# T09_LockBox_ver6.net
KiCad netlist of a schematic drawn in EAGLE
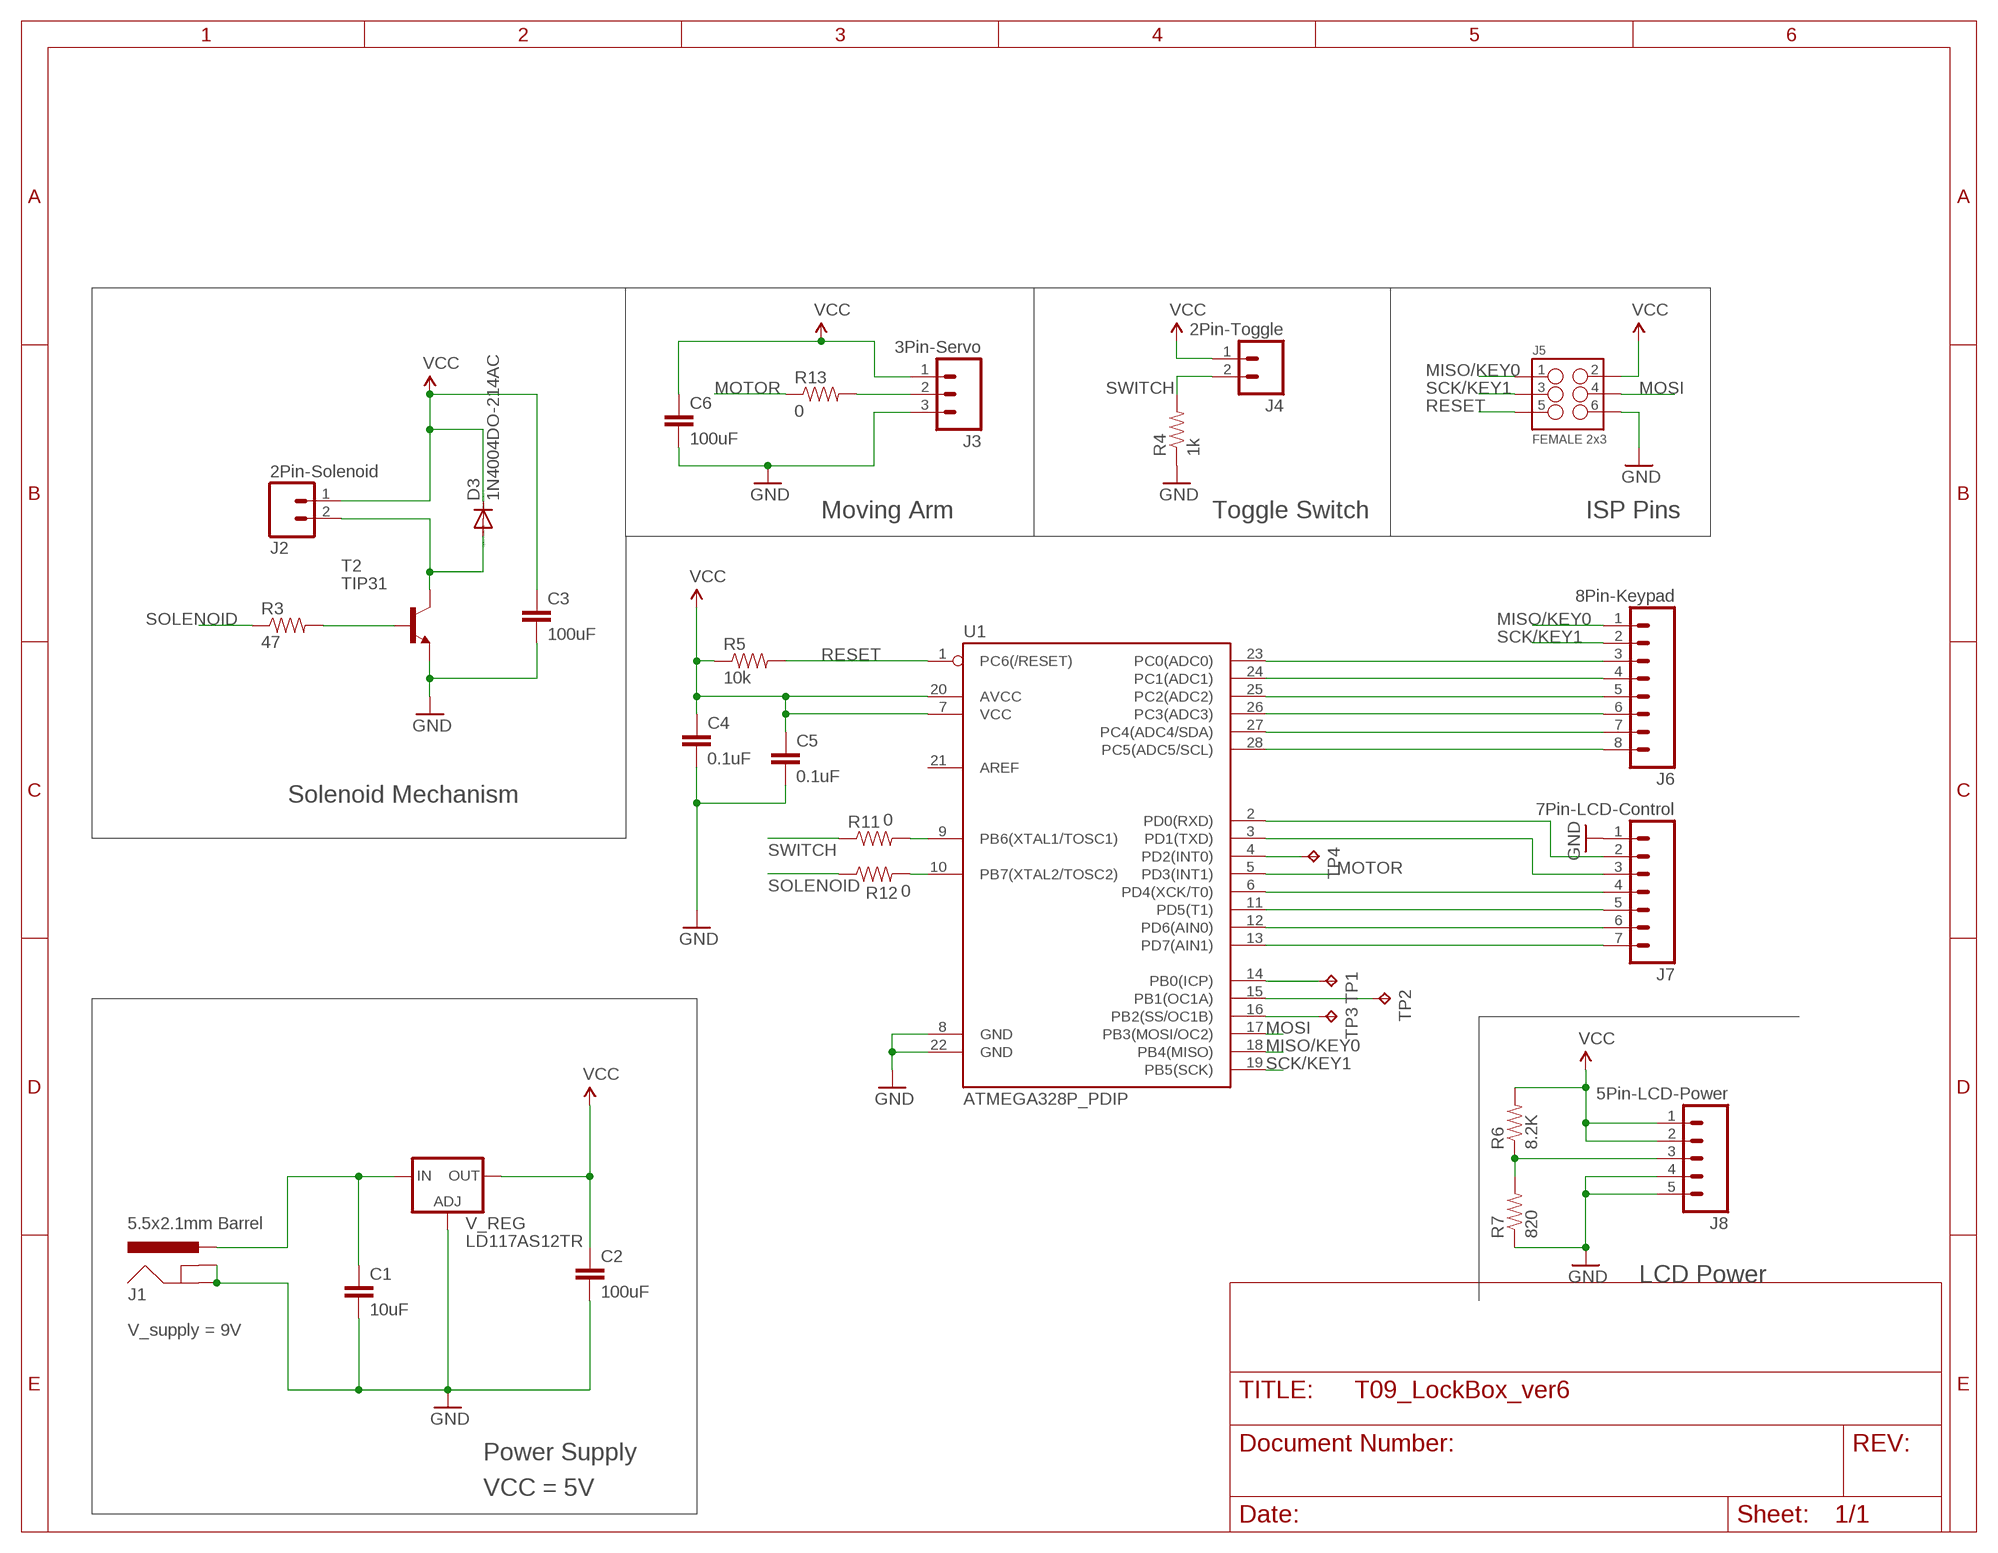
[diagram p0: schematic, sheet 1]

(export (version "E")
  (design (tool "Eeschema 10.0.6"))
  (components
    (comp (ref "C1")
      (value "10uF")
      (footprint "eagle-import:0603-CAP")
      (libsource (lib "eagle-import") (part "CAP0603-CAP"))
    )
    (comp (ref "C2")
      (value "100uF")
      (footprint "eagle-import:0603-CAP")
      (libsource (lib "eagle-import") (part "CAP0603-CAP"))
    )
    (comp (ref "C3")
      (value "100uF")
      (footprint "eagle-import:0603-CAP")
      (libsource (lib "eagle-import") (part "CAP0603-CAP"))
    )
    (comp (ref "C4")
      (value "0.1uF")
      (footprint "eagle-import:0603-CAP")
      (libsource (lib "eagle-import") (part "CAP0603-CAP"))
    )
    (comp (ref "C5")
      (value "0.1uF")
      (footprint "eagle-import:0603-CAP")
      (libsource (lib "eagle-import") (part "CAP0603-CAP"))
    )
    (comp (ref "C6")
      (value "100uF")
      (footprint "eagle-import:0603-CAP")
      (libsource (lib "eagle-import") (part "CAP0603-CAP"))
    )
    (comp (ref "D3")
      (value "1N4004DO-214AC")
      (footprint "eagle-import:DO-214AC")
      (libsource (lib "eagle-import") (part "1N4004DO-214AC"))
    )
    (comp (ref "J1")
      (value "5.5x2.1mm Barrel")
      (footprint "eagle-import:POWER_JACK_SMD")
      (libsource (lib "eagle-import") (part "POWER_JACKSMD"))
    )
    (comp (ref "J2")
      (value "2Pin-Solenoid")
      (footprint "eagle-import:1X02")
      (libsource (lib "eagle-import") (part "M02PTH"))
    )
    (comp (ref "J3")
      (value "3Pin-Servo")
      (footprint "eagle-import:1X03")
      (libsource (lib "eagle-import") (part "M03PTH"))
    )
    (comp (ref "J4")
      (value "2Pin-Toggle")
      (footprint "eagle-import:1X02")
      (libsource (lib "eagle-import") (part "M02PTH"))
    )
    (comp (ref "J5")
      (value "FEMALE 2x3")
      (footprint "eagle-import:2X3")
      (libsource (lib "eagle-import") (part "M03X2FEMALE"))
    )
    (comp (ref "J6")
      (value "8Pin-Keypad")
      (footprint "eagle-import:1X08_ROUND")
      (libsource (lib "eagle-import") (part "M08"))
    )
    (comp (ref "J7")
      (value "7Pin-LCD-Control")
      (footprint "eagle-import:1X07")
      (libsource (lib "eagle-import") (part "M07"))
    )
    (comp (ref "J8")
      (value "5Pin-LCD-Power")
      (footprint "eagle-import:1X05")
      (libsource (lib "eagle-import") (part "M05PTH"))
    )
    (comp (ref "R3")
      (value "47")
      (footprint "eagle-import:0805")
      (libsource (lib "eagle-import") (part "RESISTOR0805-RES"))
    )
    (comp (ref "R4")
      (value "1k")
      (footprint "eagle-import:0603-RES")
      (libsource (lib "eagle-import") (part "RESISTOR0603"))
    )
    (comp (ref "R5")
      (value "10k")
      (footprint "eagle-import:0603-RES")
      (libsource (lib "eagle-import") (part "RESISTOR0603"))
    )
    (comp (ref "R6")
      (value "8.2K")
      (footprint "eagle-import:0603-RES")
      (libsource (lib "eagle-import") (part "RESISTOR0603"))
    )
    (comp (ref "R7")
      (value "820")
      (footprint "eagle-import:0603-RES")
      (libsource (lib "eagle-import") (part "RESISTOR0603"))
    )
    (comp (ref "R11")
      (value "0")
      (footprint "eagle-import:0603-RES")
      (libsource (lib "eagle-import") (part "RESISTOR0603"))
    )
    (comp (ref "R12")
      (value "0")
      (footprint "eagle-import:0603-RES")
      (libsource (lib "eagle-import") (part "RESISTOR0603"))
    )
    (comp (ref "R13")
      (value "0")
      (footprint "eagle-import:0603-RES")
      (libsource (lib "eagle-import") (part "RESISTOR0603"))
    )
    (comp (ref "T2")
      (value "TIP31")
      (footprint "eagle-import:TO220")
      (libsource (lib "eagle-import") (part "TIP31"))
    )
    (comp (ref "TP1")
      (value "TPPAD1-13")
      (footprint "eagle-import:P1-13")
      (libsource (lib "eagle-import") (part "TPPAD1-13"))
    )
    (comp (ref "TP2")
      (value "TPPAD1-13")
      (footprint "eagle-import:P1-13")
      (libsource (lib "eagle-import") (part "TPPAD1-13"))
    )
    (comp (ref "TP3")
      (value "TPPAD1-13")
      (footprint "eagle-import:P1-13")
      (libsource (lib "eagle-import") (part "TPPAD1-13"))
    )
    (comp (ref "TP4")
      (value "TPPAD1-13")
      (footprint "eagle-import:P1-13")
      (libsource (lib "eagle-import") (part "TPPAD1-13"))
    )
    (comp (ref "U1")
      (value "ATMEGA328P_PDIP")
      (footprint "eagle-import:DIL28-3")
      (libsource (lib "eagle-import") (part "ATMEGA328P_PDIP"))
    )
    (comp (ref "V_REG")
      (value "LD117AS12TR")
      (footprint "eagle-import:SOT223")
      (libsource (lib "eagle-import") (part "LD117A?S12TR"))
    )
  )
  (nets
    (net (code "1") (name "/MISO{slash}KEY0") (class "Default")
      (node (ref "J5") (pin "1") (pinfunction "1_1") (pintype "bidirectional"))
      (node (ref "J6") (pin "1") (pinfunction "1_1") (pintype "passive"))
      (node (ref "U1") (pin "18") (pinfunction "PB4(MISO)_18") (pintype "bidirectional"))
    )
    (net (code "2") (name "/MOSI") (class "Default")
      (node (ref "J5") (pin "4") (pinfunction "4_4") (pintype "bidirectional"))
      (node (ref "U1") (pin "17") (pinfunction "PB3(MOSI/OC2)_17") (pintype "bidirectional"))
    )
    (net (code "3") (name "/MOTOR") (class "Default")
      (node (ref "R13") (pin "1") (pinfunction "1_1") (pintype "passive"))
      (node (ref "U1") (pin "5") (pinfunction "PD3(INT1)_5") (pintype "bidirectional"))
    )
    (net (code "4") (name "/RESET") (class "Default")
      (node (ref "J5") (pin "5") (pinfunction "5_5") (pintype "bidirectional"))
      (node (ref "R5") (pin "2") (pinfunction "2_2") (pintype "passive"))
      (node (ref "U1") (pin "1") (pinfunction "PC6(/RESET)_1") (pintype "bidirectional"))
    )
    (net (code "5") (name "/SCK{slash}KEY1") (class "Default")
      (node (ref "J5") (pin "3") (pinfunction "3_3") (pintype "bidirectional"))
      (node (ref "J6") (pin "2") (pinfunction "2_2") (pintype "passive"))
      (node (ref "U1") (pin "19") (pinfunction "PB5(SCK)_19") (pintype "bidirectional"))
    )
    (net (code "6") (name "/SOLENOID") (class "Default")
      (node (ref "R12") (pin "1") (pinfunction "1_1") (pintype "passive"))
      (node (ref "R3") (pin "1") (pinfunction "1_1") (pintype "passive"))
    )
    (net (code "7") (name "/SWITCH") (class "Default")
      (node (ref "J4") (pin "2") (pinfunction "2_2") (pintype "passive"))
      (node (ref "R11") (pin "1") (pinfunction "1_1") (pintype "passive"))
      (node (ref "R4") (pin "2") (pinfunction "2_2") (pintype "passive"))
    )
    (net (code "8") (name "GND") (class "Default")
      (node (ref "C1") (pin "2") (pinfunction "2_2") (pintype "passive"))
      (node (ref "C2") (pin "2") (pinfunction "2_2") (pintype "passive"))
      (node (ref "C3") (pin "2") (pinfunction "2_2") (pintype "passive"))
      (node (ref "C4") (pin "2") (pinfunction "2_2") (pintype "passive"))
      (node (ref "C5") (pin "2") (pinfunction "2_2") (pintype "passive"))
      (node (ref "C6") (pin "2") (pinfunction "2_2") (pintype "passive"))
      (node (ref "J1") (pin "GND") (pinfunction "GNDBREAK_GND") (pintype "bidirectional"))
      (node (ref "J1") (pin "P$4") (pinfunction "GND_P$4") (pintype "bidirectional"))
      (node (ref "J3") (pin "3") (pinfunction "3_3") (pintype "passive"))
      (node (ref "J5") (pin "6") (pinfunction "6_6") (pintype "bidirectional"))
      (node (ref "J7") (pin "1") (pinfunction "1_1") (pintype "passive"))
      (node (ref "J8") (pin "4") (pinfunction "4_4") (pintype "passive"))
      (node (ref "J8") (pin "5") (pinfunction "5_5") (pintype "passive"))
      (node (ref "R4") (pin "1") (pinfunction "1_1") (pintype "passive"))
      (node (ref "R7") (pin "1") (pinfunction "1_1") (pintype "passive"))
      (node (ref "T2") (pin "3") (pinfunction "E_3") (pintype "passive"))
      (node (ref "U1") (pin "22") (pinfunction "GND_22") (pintype "bidirectional"))
      (node (ref "U1") (pin "8") (pinfunction "GND_8") (pintype "bidirectional"))
      (node (ref "V_REG") (pin "1") (pinfunction "ADJ_1") (pintype "input"))
    )
    (net (code "9") (name "Net-(J1-PWR)") (class "Default")
      (node (ref "C1") (pin "1") (pinfunction "1_1") (pintype "passive"))
      (node (ref "J1") (pin "VIN0") (pinfunction "PWR_VIN0") (pintype "bidirectional"))
      (node (ref "V_REG") (pin "3") (pinfunction "IN_3") (pintype "input"))
    )
    (net (code "10") (name "Net-(J3-Pad2)") (class "Default")
      (node (ref "J3") (pin "2") (pinfunction "2_2") (pintype "passive"))
      (node (ref "R13") (pin "2") (pinfunction "2_2") (pintype "passive"))
    )
    (net (code "11") (name "Net-(J8-Pad3)") (class "Default")
      (node (ref "J8") (pin "3") (pinfunction "3_3") (pintype "passive"))
      (node (ref "R6") (pin "1") (pinfunction "1_1") (pintype "passive"))
      (node (ref "R7") (pin "2") (pinfunction "2_2") (pintype "passive"))
    )
    (net (code "12") (name "Net-(T2-B)") (class "Default")
      (node (ref "R3") (pin "2") (pinfunction "2_2") (pintype "passive"))
      (node (ref "T2") (pin "1") (pinfunction "B_1") (pintype "passive"))
    )
    (net (code "13") (name "Net-(T2-C)") (class "Default")
      (node (ref "D3") (pin "A") (pinfunction "A_A") (pintype "passive"))
      (node (ref "J2") (pin "2") (pinfunction "2_2") (pintype "passive"))
      (node (ref "T2") (pin "2") (pinfunction "C_2") (pintype "passive"))
    )
    (net (code "14") (name "Net-(U1-PB0(ICP))") (class "Default")
      (node (ref "TP1") (pin "TP") (pinfunction "TP_TP") (pintype "input"))
      (node (ref "U1") (pin "14") (pinfunction "PB0(ICP)_14") (pintype "bidirectional"))
    )
    (net (code "15") (name "Net-(U1-PB1(OC1A))") (class "Default")
      (node (ref "TP2") (pin "TP") (pinfunction "TP_TP") (pintype "input"))
      (node (ref "U1") (pin "15") (pinfunction "PB1(OC1A)_15") (pintype "bidirectional"))
    )
    (net (code "16") (name "Net-(U1-PB2(SS{slash}OC1B))") (class "Default")
      (node (ref "TP3") (pin "TP") (pinfunction "TP_TP") (pintype "input"))
      (node (ref "U1") (pin "16") (pinfunction "PB2(SS/OC1B)_16") (pintype "bidirectional"))
    )
    (net (code "17") (name "Net-(U1-PB6(XTAL1{slash}TOSC1))") (class "Default")
      (node (ref "R11") (pin "2") (pinfunction "2_2") (pintype "passive"))
      (node (ref "U1") (pin "9") (pinfunction "PB6(XTAL1/TOSC1)_9") (pintype "bidirectional"))
    )
    (net (code "18") (name "Net-(U1-PB7(XTAL2{slash}TOSC2))") (class "Default")
      (node (ref "R12") (pin "2") (pinfunction "2_2") (pintype "passive"))
      (node (ref "U1") (pin "10") (pinfunction "PB7(XTAL2/TOSC2)_10") (pintype "bidirectional"))
    )
    (net (code "19") (name "Net-(U1-PC0(ADC0))") (class "Default")
      (node (ref "J6") (pin "3") (pinfunction "3_3") (pintype "passive"))
      (node (ref "U1") (pin "23") (pinfunction "PC0(ADC0)_23") (pintype "bidirectional"))
    )
    (net (code "20") (name "Net-(U1-PC1(ADC1))") (class "Default")
      (node (ref "J6") (pin "4") (pinfunction "4_4") (pintype "passive"))
      (node (ref "U1") (pin "24") (pinfunction "PC1(ADC1)_24") (pintype "bidirectional"))
    )
    (net (code "21") (name "Net-(U1-PC2(ADC2))") (class "Default")
      (node (ref "J6") (pin "5") (pinfunction "5_5") (pintype "passive"))
      (node (ref "U1") (pin "25") (pinfunction "PC2(ADC2)_25") (pintype "bidirectional"))
    )
    (net (code "22") (name "Net-(U1-PC3(ADC3))") (class "Default")
      (node (ref "J6") (pin "6") (pinfunction "6_6") (pintype "passive"))
      (node (ref "U1") (pin "26") (pinfunction "PC3(ADC3)_26") (pintype "bidirectional"))
    )
    (net (code "23") (name "Net-(U1-PC4(ADC4{slash}SDA))") (class "Default")
      (node (ref "J6") (pin "7") (pinfunction "7_7") (pintype "passive"))
      (node (ref "U1") (pin "27") (pinfunction "PC4(ADC4/SDA)_27") (pintype "bidirectional"))
    )
    (net (code "24") (name "Net-(U1-PC5(ADC5{slash}SCL))") (class "Default")
      (node (ref "J6") (pin "8") (pinfunction "8_8") (pintype "passive"))
      (node (ref "U1") (pin "28") (pinfunction "PC5(ADC5/SCL)_28") (pintype "bidirectional"))
    )
    (net (code "25") (name "Net-(U1-PD0(RXD))") (class "Default")
      (node (ref "J7") (pin "2") (pinfunction "2_2") (pintype "passive"))
      (node (ref "U1") (pin "2") (pinfunction "PD0(RXD)_2") (pintype "bidirectional"))
    )
    (net (code "26") (name "Net-(U1-PD1(TXD))") (class "Default")
      (node (ref "J7") (pin "3") (pinfunction "3_3") (pintype "passive"))
      (node (ref "U1") (pin "3") (pinfunction "PD1(TXD)_3") (pintype "bidirectional"))
    )
    (net (code "27") (name "Net-(U1-PD2(INT0))") (class "Default")
      (node (ref "TP4") (pin "TP") (pinfunction "TP_TP") (pintype "input"))
      (node (ref "U1") (pin "4") (pinfunction "PD2(INT0)_4") (pintype "bidirectional"))
    )
    (net (code "28") (name "Net-(U1-PD4(XCK{slash}T0))") (class "Default")
      (node (ref "J7") (pin "4") (pinfunction "4_4") (pintype "passive"))
      (node (ref "U1") (pin "6") (pinfunction "PD4(XCK/T0)_6") (pintype "bidirectional"))
    )
    (net (code "29") (name "Net-(U1-PD5(T1))") (class "Default")
      (node (ref "J7") (pin "5") (pinfunction "5_5") (pintype "passive"))
      (node (ref "U1") (pin "11") (pinfunction "PD5(T1)_11") (pintype "bidirectional"))
    )
    (net (code "30") (name "Net-(U1-PD6(AIN0))") (class "Default")
      (node (ref "J7") (pin "6") (pinfunction "6_6") (pintype "passive"))
      (node (ref "U1") (pin "12") (pinfunction "PD6(AIN0)_12") (pintype "bidirectional"))
    )
    (net (code "31") (name "Net-(U1-PD7(AIN1))") (class "Default")
      (node (ref "J7") (pin "7") (pinfunction "7_7") (pintype "passive"))
      (node (ref "U1") (pin "13") (pinfunction "PD7(AIN1)_13") (pintype "bidirectional"))
    )
    (net (code "32") (name "VCC") (class "Default")
      (node (ref "C2") (pin "1") (pinfunction "1_1") (pintype "passive"))
      (node (ref "C3") (pin "1") (pinfunction "1_1") (pintype "passive"))
      (node (ref "C4") (pin "1") (pinfunction "1_1") (pintype "passive"))
      (node (ref "C5") (pin "1") (pinfunction "1_1") (pintype "passive"))
      (node (ref "C6") (pin "1") (pinfunction "1_1") (pintype "passive"))
      (node (ref "D3") (pin "C") (pinfunction "C_C") (pintype "passive"))
      (node (ref "J2") (pin "1") (pinfunction "1_1") (pintype "passive"))
      (node (ref "J3") (pin "1") (pinfunction "1_1") (pintype "passive"))
      (node (ref "J4") (pin "1") (pinfunction "1_1") (pintype "passive"))
      (node (ref "J5") (pin "2") (pinfunction "2_2") (pintype "bidirectional"))
      (node (ref "J8") (pin "1") (pinfunction "1_1") (pintype "passive"))
      (node (ref "J8") (pin "2") (pinfunction "2_2") (pintype "passive"))
      (node (ref "R5") (pin "1") (pinfunction "1_1") (pintype "passive"))
      (node (ref "R6") (pin "2") (pinfunction "2_2") (pintype "passive"))
      (node (ref "U1") (pin "20") (pinfunction "AVCC_20") (pintype "bidirectional"))
      (node (ref "U1") (pin "7") (pinfunction "VCC_7") (pintype "bidirectional"))
      (node (ref "V_REG") (pin "4") (pinfunction "OUT_4") (pintype "passive"))
    )
    (net (code "33") (name "unconnected-(U1-AREF-Pad21)") (class "Default")
      (node (ref "U1") (pin "21") (pinfunction "AREF_21") (pintype "bidirectional"))
    )
  )
)
